# Sheet1.net
KiCad netlist of a schematic drawn in Altium Designer
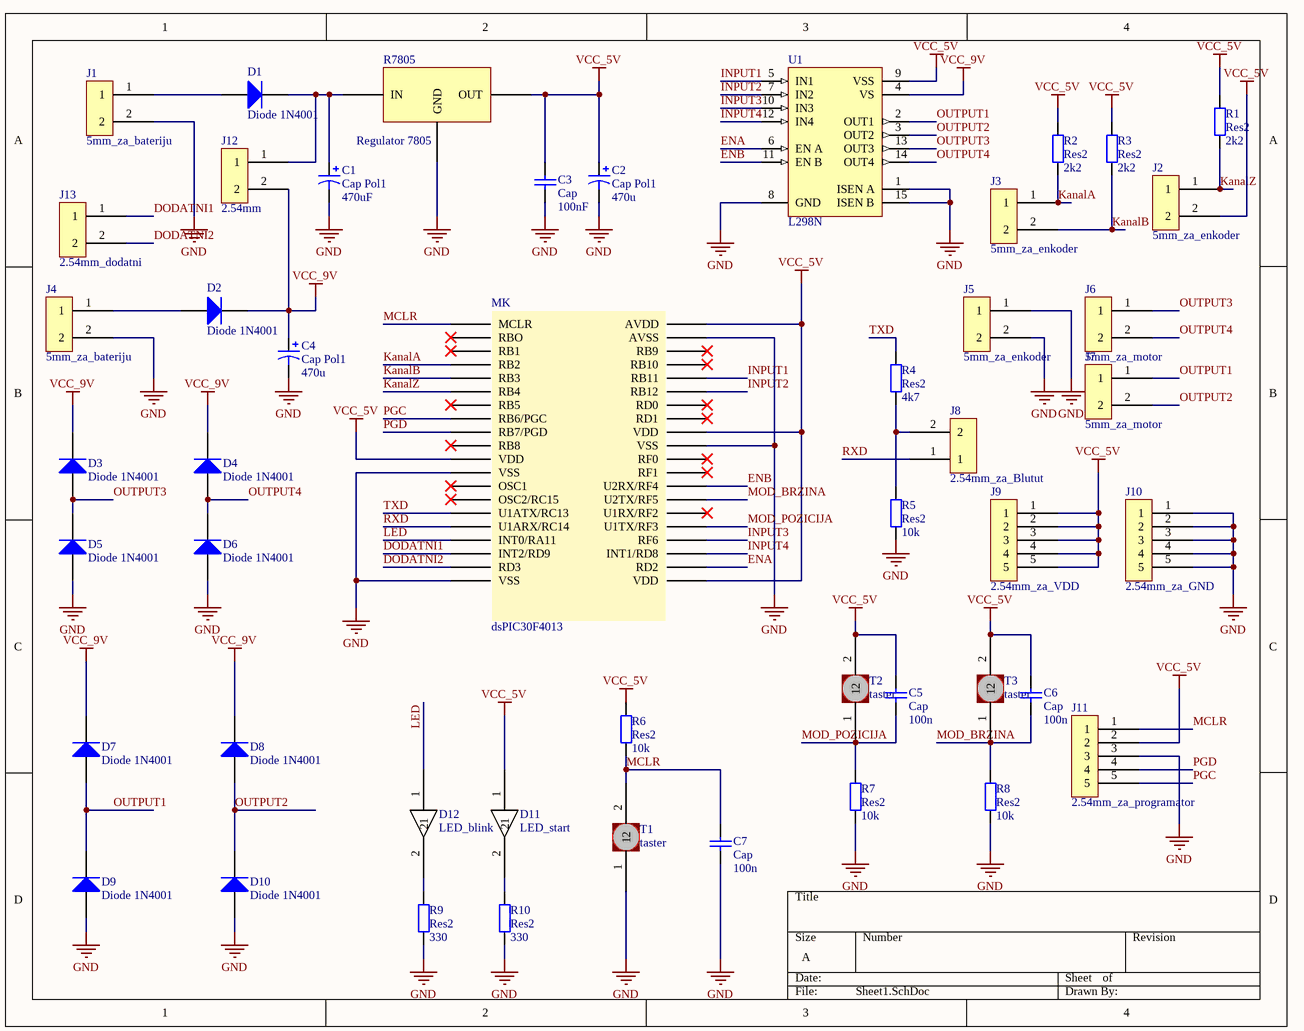
[diagram p0: Sheet1.SchDoc]

(export (version "E")
  (design (tool "Eeschema 10.0.6"))
  (components
    (comp (ref "C1")
      (value "Cap Pol1")
      (footprint "RB7.6-15")
      (description "Polarized Capacitor (Radial)")
      (fields (field (name "ALTIUM_VALUE") "470uF") (field (name "PUBLISHER") "Altium Limited"))
      (libsource (lib "Miscellaneous Devices") (part "Cap Pol1"))
    )
    (comp (ref "C2")
      (value "Cap Pol1")
      (footprint "RB7.6-15")
      (description "Polarized Capacitor (Radial)")
      (fields (field (name "ALTIUM_VALUE") "470u") (field (name "PUBLISHER") "Altium Limited"))
      (libsource (lib "Miscellaneous Devices") (part "Cap Pol1"))
    )
    (comp (ref "C3")
      (value "Cap")
      (footprint "RAD-0.3")
      (description "Capacitor")
      (fields (field (name "ALTIUM_VALUE") "100nF") (field (name "PUBLISHER") "Altium Limited"))
      (libsource (lib "Miscellaneous Devices") (part "Cap"))
    )
    (comp (ref "C4")
      (value "Cap Pol1")
      (footprint "RB7.6-15")
      (description "Polarized Capacitor (Radial)")
      (fields (field (name "ALTIUM_VALUE") "470u") (field (name "PUBLISHER") "Altium Limited"))
      (libsource (lib "Miscellaneous Devices") (part "Cap Pol1"))
    )
    (comp (ref "C5")
      (value "Cap")
      (footprint "RAD-0.3")
      (description "Capacitor")
      (fields (field (name "ALTIUM_VALUE") "100n") (field (name "PUBLISHER") "Altium Limited"))
      (libsource (lib "Miscellaneous Devices") (part "Cap"))
    )
    (comp (ref "C6")
      (value "Cap")
      (footprint "RAD-0.3")
      (description "Capacitor")
      (fields (field (name "ALTIUM_VALUE") "100n") (field (name "PUBLISHER") "Altium Limited"))
      (libsource (lib "Miscellaneous Devices") (part "Cap"))
    )
    (comp (ref "C7")
      (value "Cap")
      (footprint "RAD-0.3")
      (description "Capacitor")
      (fields (field (name "ALTIUM_VALUE") "100n") (field (name "PUBLISHER") "Altium Limited"))
      (libsource (lib "Miscellaneous Devices") (part "Cap"))
    )
    (comp (ref "D1")
      (value "Diode 1N4001")
      (footprint "DO-41")
      (description "1 Amp General Purpose Rectifier")
      (fields (field (name "PUBLISHER") "Altium Limited"))
      (libsource (lib "Miscellaneous Devices") (part "Diode 1N4001"))
    )
    (comp (ref "D2")
      (value "Diode 1N4001")
      (footprint "DO-41")
      (description "1 Amp General Purpose Rectifier")
      (fields (field (name "PUBLISHER") "Altium Limited"))
      (libsource (lib "Miscellaneous Devices") (part "Diode 1N4001"))
    )
    (comp (ref "D3")
      (value "Diode 1N4001")
      (footprint "DO-41")
      (description "1 Amp General Purpose Rectifier")
      (fields (field (name "PUBLISHER") "Altium Limited"))
      (libsource (lib "Miscellaneous Devices") (part "Diode 1N4001"))
    )
    (comp (ref "D4")
      (value "Diode 1N4001")
      (footprint "DO-41")
      (description "1 Amp General Purpose Rectifier")
      (fields (field (name "PUBLISHER") "Altium Limited"))
      (libsource (lib "Miscellaneous Devices") (part "Diode 1N4001"))
    )
    (comp (ref "D5")
      (value "Diode 1N4001")
      (footprint "DO-41")
      (description "1 Amp General Purpose Rectifier")
      (fields (field (name "PUBLISHER") "Altium Limited"))
      (libsource (lib "Miscellaneous Devices") (part "Diode 1N4001"))
    )
    (comp (ref "D6")
      (value "Diode 1N4001")
      (footprint "DO-41")
      (description "1 Amp General Purpose Rectifier")
      (fields (field (name "PUBLISHER") "Altium Limited"))
      (libsource (lib "Miscellaneous Devices") (part "Diode 1N4001"))
    )
    (comp (ref "D7")
      (value "Diode 1N4001")
      (footprint "DO-41")
      (description "1 Amp General Purpose Rectifier")
      (fields (field (name "PUBLISHER") "Altium Limited"))
      (libsource (lib "Miscellaneous Devices") (part "Diode 1N4001"))
    )
    (comp (ref "D8")
      (value "Diode 1N4001")
      (footprint "DO-41")
      (description "1 Amp General Purpose Rectifier")
      (fields (field (name "PUBLISHER") "Altium Limited"))
      (libsource (lib "Miscellaneous Devices") (part "Diode 1N4001"))
    )
    (comp (ref "D9")
      (value "Diode 1N4001")
      (footprint "DO-41")
      (description "1 Amp General Purpose Rectifier")
      (fields (field (name "PUBLISHER") "Altium Limited"))
      (libsource (lib "Miscellaneous Devices") (part "Diode 1N4001"))
    )
    (comp (ref "D10")
      (value "Diode 1N4001")
      (footprint "DO-41")
      (description "1 Amp General Purpose Rectifier")
      (fields (field (name "PUBLISHER") "Altium Limited"))
      (libsource (lib "Miscellaneous Devices") (part "Diode 1N4001"))
    )
    (comp (ref "D11")
      (value "LED_start")
      (footprint "PcbLib5:PCBComponent_1")
      (libsource (lib "Schlib5") (part "Component_1"))
    )
    (comp (ref "D12")
      (value "LED_blink")
      (footprint "PcbLib5:PCBComponent_1")
      (libsource (lib "Schlib5") (part "Component_1"))
    )
    (comp (ref "J1")
      (value "5mm_za_bateriju")
      (footprint "PcbLib4:PCBComponent_1")
      (libsource (lib "Schlib4") (part "Component_1"))
    )
    (comp (ref "J2")
      (value "5mm_za_enkoder")
      (footprint "PcbLib4:PCBComponent_1")
      (libsource (lib "Schlib4") (part "Component_1"))
    )
    (comp (ref "J3")
      (value "5mm_za_enkoder")
      (footprint "PcbLib4:PCBComponent_1")
      (libsource (lib "Schlib4") (part "Component_1"))
    )
    (comp (ref "J4")
      (value "5mm_za_bateriju")
      (footprint "PcbLib4:PCBComponent_1")
      (libsource (lib "Schlib4") (part "Component_1"))
    )
    (comp (ref "J5")
      (value "5mm_za_enkoder")
      (footprint "PcbLib4:PCBComponent_1")
      (libsource (lib "Schlib4") (part "Component_1"))
    )
    (comp (ref "J6")
      (value "5mm_za_motor")
      (footprint "PcbLib4:PCBComponent_1")
      (libsource (lib "Schlib4") (part "Component_1"))
    )
    (comp (ref "J7")
      (value "5mm_za_motor")
      (footprint "PcbLib4:PCBComponent_1")
      (libsource (lib "Schlib4") (part "Component_1"))
    )
    (comp (ref "J8")
      (value "2.54mm_za_Blutut")
      (footprint "PcbLib3:PCBComponent_1")
      (libsource (lib "") (part "Component_1_1"))
    )
    (comp (ref "J9")
      (value "2.54mm_za_VDD")
      (footprint "PcbLib7:PCBComponent_1")
      (libsource (lib "Schlib7") (part "Component_1"))
    )
    (comp (ref "J10")
      (value "2.54mm_za_GND")
      (footprint "PcbLib7:PCBComponent_1")
      (libsource (lib "Schlib7") (part "Component_1"))
    )
    (comp (ref "J11")
      (value "2.54mm_za_programator")
      (footprint "PcbLib7:PCBComponent_1")
      (libsource (lib "Schlib7") (part "Component_1"))
    )
    (comp (ref "J12")
      (value "2.54mm")
      (footprint "PcbLib3:PCBComponent_1")
      (libsource (lib "Schlib1") (part "Component_1"))
    )
    (comp (ref "J13")
      (value "2.54mm_dodatni")
      (footprint "PcbLib3:PCBComponent_1")
      (libsource (lib "Schlib1") (part "Component_1"))
    )
    (comp (ref "MK")
      (value "dsPIC30F4013")
      (footprint "PcbLib1:PCBComponent_1")
      (libsource (lib "Schlib3") (part "Component_1"))
    )
    (comp (ref "R1")
      (value "Res2")
      (footprint "AXIAL-0.4")
      (description "Resistor")
      (fields (field (name "ALTIUM_VALUE") "2k2") (field (name "PUBLISHER") "Altium Limited"))
      (libsource (lib "Miscellaneous Devices") (part "Res2"))
    )
    (comp (ref "R2")
      (value "Res2")
      (footprint "AXIAL-0.4")
      (description "Resistor")
      (fields (field (name "ALTIUM_VALUE") "2k2") (field (name "PUBLISHER") "Altium Limited"))
      (libsource (lib "Miscellaneous Devices") (part "Res2"))
    )
    (comp (ref "R3")
      (value "Res2")
      (footprint "AXIAL-0.4")
      (description "Resistor")
      (fields (field (name "ALTIUM_VALUE") "2k2") (field (name "PUBLISHER") "Altium Limited"))
      (libsource (lib "Miscellaneous Devices") (part "Res2"))
    )
    (comp (ref "R4")
      (value "Res2")
      (footprint "AXIAL-0.4")
      (description "Resistor")
      (fields (field (name "ALTIUM_VALUE") "4k7") (field (name "PUBLISHER") "Altium Limited"))
      (libsource (lib "Miscellaneous Devices") (part "Res2"))
    )
    (comp (ref "R5")
      (value "Res2")
      (footprint "AXIAL-0.4")
      (description "Resistor")
      (fields (field (name "ALTIUM_VALUE") "10k") (field (name "PUBLISHER") "Altium Limited"))
      (libsource (lib "Miscellaneous Devices") (part "Res2"))
    )
    (comp (ref "R6")
      (value "Res2")
      (footprint "AXIAL-0.4")
      (description "Resistor")
      (fields (field (name "ALTIUM_VALUE") "10k") (field (name "PUBLISHER") "Altium Limited"))
      (libsource (lib "Miscellaneous Devices") (part "Res2"))
    )
    (comp (ref "R7")
      (value "Res2")
      (footprint "AXIAL-0.4")
      (description "Resistor")
      (fields (field (name "ALTIUM_VALUE") "10k") (field (name "PUBLISHER") "Altium Limited"))
      (libsource (lib "Miscellaneous Devices") (part "Res2"))
    )
    (comp (ref "R8")
      (value "Res2")
      (footprint "AXIAL-0.4")
      (description "Resistor")
      (fields (field (name "ALTIUM_VALUE") "10k") (field (name "PUBLISHER") "Altium Limited"))
      (libsource (lib "Miscellaneous Devices") (part "Res2"))
    )
    (comp (ref "R9")
      (value "Res2")
      (footprint "AXIAL-0.4")
      (description "Resistor")
      (fields (field (name "ALTIUM_VALUE") "330") (field (name "PUBLISHER") "Altium Limited"))
      (libsource (lib "Miscellaneous Devices") (part "Res2"))
    )
    (comp (ref "R10")
      (value "Res2")
      (footprint "AXIAL-0.4")
      (description "Resistor")
      (fields (field (name "ALTIUM_VALUE") "330") (field (name "PUBLISHER") "Altium Limited"))
      (libsource (lib "Miscellaneous Devices") (part "Res2"))
    )
    (comp (ref "R7805")
      (value "Regulator 7805")
      (footprint "PCBComponent_1")
      (libsource (lib "Schlib2") (part "Component_1"))
    )
    (comp (ref "T1")
      (value "taster")
      (footprint "PcbLib6:PCBComponent_1")
      (libsource (lib "Schlib6") (part "Component_1"))
    )
    (comp (ref "T2")
      (value "taster")
      (footprint "PcbLib6:PCBComponent_1")
      (libsource (lib "Schlib6") (part "Component_1"))
    )
    (comp (ref "T3")
      (value "taster")
      (footprint "PcbLib6:PCBComponent_1")
      (libsource (lib "Schlib6") (part "Component_1"))
    )
    (comp (ref "U1")
      (value "L298N")
      (footprint "Multiwatt15V")
      (description "Dual Full Bridge Driver")
      (fields (field (name "PUBLISHER") "Altium Limited"))
      (libsource (lib "ST Interface DC Motor Controller") (part "L298N"))
    )
  )
  (nets
    (net (code "1") (name "/DODATNI1") (class "Default")
      (node (ref "J13") (pin "1") (pinfunction "1_1") (pintype "passive"))
      (node (ref "MK") (pin "18") (pinfunction "INT2/RD9_18") (pintype "passive"))
    )
    (net (code "2") (name "/DODATNI2") (class "Default")
      (node (ref "J13") (pin "2") (pinfunction "2_2") (pintype "passive"))
      (node (ref "MK") (pin "19") (pinfunction "RD3_19") (pintype "passive"))
    )
    (net (code "3") (name "/ENA") (class "Default")
      (node (ref "MK") (pin "22") (pinfunction "RD2_22") (pintype "passive"))
      (node (ref "U1") (pin "6") (pinfunction "EN_A_6") (pintype "input"))
    )
    (net (code "4") (name "/ENB") (class "Default")
      (node (ref "MK") (pin "28") (pinfunction "U2RX/RF4_28") (pintype "passive"))
      (node (ref "U1") (pin "11") (pinfunction "EN_B_11") (pintype "input"))
    )
    (net (code "5") (name "/INPUT1") (class "Default")
      (node (ref "MK") (pin "36") (pinfunction "RB11_36") (pintype "passive"))
      (node (ref "U1") (pin "5") (pinfunction "IN1_5") (pintype "input"))
    )
    (net (code "6") (name "/INPUT2") (class "Default")
      (node (ref "MK") (pin "35") (pinfunction "RB12_35") (pintype "passive"))
      (node (ref "U1") (pin "7") (pinfunction "IN2_7") (pintype "input"))
    )
    (net (code "7") (name "/INPUT3") (class "Default")
      (node (ref "MK") (pin "24") (pinfunction "RF6_24") (pintype "passive"))
      (node (ref "U1") (pin "10") (pinfunction "IN3_10") (pintype "input"))
    )
    (net (code "8") (name "/INPUT4") (class "Default")
      (node (ref "MK") (pin "23") (pinfunction "INT1/RD8_23") (pintype "passive"))
      (node (ref "U1") (pin "12") (pinfunction "IN4_12") (pintype "input"))
    )
    (net (code "9") (name "/KanalA") (class "Default")
      (node (ref "J3") (pin "1") (pinfunction "1_1") (pintype "passive"))
      (node (ref "MK") (pin "4") (pinfunction "RB2_4") (pintype "passive"))
      (node (ref "R2") (pin "1") (pinfunction "1_1") (pintype "passive"))
    )
    (net (code "10") (name "/KanalB") (class "Default")
      (node (ref "J3") (pin "2") (pinfunction "2_2") (pintype "passive"))
      (node (ref "MK") (pin "5") (pinfunction "RB3_5") (pintype "passive"))
      (node (ref "R3") (pin "1") (pinfunction "1_1") (pintype "passive"))
    )
    (net (code "11") (name "/KanalZ") (class "Default")
      (node (ref "J2") (pin "1") (pinfunction "1_1") (pintype "passive"))
      (node (ref "MK") (pin "6") (pinfunction "RB4_6") (pintype "passive"))
      (node (ref "R1") (pin "1") (pinfunction "1_1") (pintype "passive"))
    )
    (net (code "12") (name "/LED") (class "Default")
      (node (ref "D12") (pin "1") (pinfunction "1_1") (pintype "passive"))
      (node (ref "MK") (pin "17") (pinfunction "INT0/RA11_17") (pintype "passive"))
    )
    (net (code "13") (name "/MCLR") (class "Default")
      (node (ref "C7") (pin "2") (pinfunction "2_2") (pintype "passive"))
      (node (ref "J11") (pin "1") (pinfunction "1_1") (pintype "passive"))
      (node (ref "MK") (pin "1") (pinfunction "MCLR_1") (pintype "passive"))
      (node (ref "R6") (pin "1") (pinfunction "1_1") (pintype "passive"))
      (node (ref "T1") (pin "2") (pinfunction "2_2") (pintype "passive"))
    )
    (net (code "14") (name "/MOD_BRZINA") (class "Default")
      (node (ref "C6") (pin "1") (pinfunction "1_1") (pintype "passive"))
      (node (ref "MK") (pin "27") (pinfunction "U2TX/RF5_27") (pintype "passive"))
      (node (ref "R8") (pin "2") (pinfunction "2_2") (pintype "passive"))
      (node (ref "T3") (pin "1") (pinfunction "1_1") (pintype "passive"))
    )
    (net (code "15") (name "/MOD_POZICIJA") (class "Default")
      (node (ref "C5") (pin "1") (pinfunction "1_1") (pintype "passive"))
      (node (ref "MK") (pin "25") (pinfunction "U1TX/RF3_25") (pintype "passive"))
      (node (ref "R7") (pin "2") (pinfunction "2_2") (pintype "passive"))
      (node (ref "T2") (pin "1") (pinfunction "1_1") (pintype "passive"))
    )
    (net (code "16") (name "/OUTPUT1") (class "Default")
      (node (ref "D7") (pin "1") (pinfunction "A_1") (pintype "passive"))
      (node (ref "D9") (pin "2") (pinfunction "K_2") (pintype "passive"))
      (node (ref "J7") (pin "1") (pinfunction "1_1") (pintype "passive"))
      (node (ref "U1") (pin "2") (pinfunction "OUT1_2") (pintype "output"))
    )
    (net (code "17") (name "/OUTPUT2") (class "Default")
      (node (ref "D10") (pin "2") (pinfunction "K_2") (pintype "passive"))
      (node (ref "D8") (pin "1") (pinfunction "A_1") (pintype "passive"))
      (node (ref "J7") (pin "2") (pinfunction "2_2") (pintype "passive"))
      (node (ref "U1") (pin "3") (pinfunction "OUT2_3") (pintype "output"))
    )
    (net (code "18") (name "/OUTPUT3") (class "Default")
      (node (ref "D3") (pin "1") (pinfunction "A_1") (pintype "passive"))
      (node (ref "D5") (pin "2") (pinfunction "K_2") (pintype "passive"))
      (node (ref "J6") (pin "1") (pinfunction "1_1") (pintype "passive"))
      (node (ref "U1") (pin "13") (pinfunction "OUT3_13") (pintype "output"))
    )
    (net (code "19") (name "/OUTPUT4") (class "Default")
      (node (ref "D4") (pin "1") (pinfunction "A_1") (pintype "passive"))
      (node (ref "D6") (pin "2") (pinfunction "K_2") (pintype "passive"))
      (node (ref "J6") (pin "2") (pinfunction "2_2") (pintype "passive"))
      (node (ref "U1") (pin "14") (pinfunction "OUT4_14") (pintype "output"))
    )
    (net (code "20") (name "/PGC") (class "Default")
      (node (ref "J11") (pin "5") (pinfunction "5_5") (pintype "passive"))
      (node (ref "MK") (pin "8") (pinfunction "RB6/PGC_8") (pintype "passive"))
    )
    (net (code "21") (name "/PGD") (class "Default")
      (node (ref "J11") (pin "4") (pinfunction "4_4") (pintype "passive"))
      (node (ref "MK") (pin "9") (pinfunction "RB7/PGD_9") (pintype "passive"))
    )
    (net (code "22") (name "/RXD") (class "Default")
      (node (ref "J8") (pin "1") (pinfunction "1_1") (pintype "passive"))
      (node (ref "MK") (pin "16") (pinfunction "U1ARX/RC14_16") (pintype "passive"))
    )
    (net (code "23") (name "/TXD") (class "Default")
      (node (ref "MK") (pin "15") (pinfunction "U1ATX/RC13_15") (pintype "passive"))
      (node (ref "R4") (pin "2") (pinfunction "2_2") (pintype "passive"))
    )
    (net (code "24") (name "GND") (class "Default")
      (node (ref "C1") (pin "2") (pinfunction "2_2") (pintype "passive"))
      (node (ref "C2") (pin "2") (pinfunction "2_2") (pintype "passive"))
      (node (ref "C3") (pin "1") (pinfunction "1_1") (pintype "passive"))
      (node (ref "C4") (pin "2") (pinfunction "2_2") (pintype "passive"))
      (node (ref "C7") (pin "1") (pinfunction "1_1") (pintype "passive"))
      (node (ref "D10") (pin "1") (pinfunction "A_1") (pintype "passive"))
      (node (ref "D5") (pin "1") (pinfunction "A_1") (pintype "passive"))
      (node (ref "D6") (pin "1") (pinfunction "A_1") (pintype "passive"))
      (node (ref "D9") (pin "1") (pinfunction "A_1") (pintype "passive"))
      (node (ref "J1") (pin "2") (pinfunction "2_2") (pintype "passive"))
      (node (ref "J10") (pin "1") (pinfunction "1_1") (pintype "passive"))
      (node (ref "J10") (pin "2") (pinfunction "2_2") (pintype "passive"))
      (node (ref "J10") (pin "3") (pinfunction "3_3") (pintype "passive"))
      (node (ref "J10") (pin "4") (pinfunction "4_4") (pintype "passive"))
      (node (ref "J10") (pin "5") (pinfunction "5_5") (pintype "passive"))
      (node (ref "J11") (pin "3") (pinfunction "3_3") (pintype "passive"))
      (node (ref "J4") (pin "2") (pinfunction "2_2") (pintype "passive"))
      (node (ref "J5") (pin "1") (pinfunction "1_1") (pintype "passive"))
      (node (ref "J5") (pin "2") (pinfunction "2_2") (pintype "passive"))
      (node (ref "MK") (pin "12") (pinfunction "VSS_12") (pintype "passive"))
      (node (ref "MK") (pin "20") (pinfunction "VSS_20") (pintype "passive"))
      (node (ref "MK") (pin "31") (pinfunction "VSS_31") (pintype "passive"))
      (node (ref "MK") (pin "39") (pinfunction "AVSS_39") (pintype "passive"))
      (node (ref "R10") (pin "1") (pinfunction "1_1") (pintype "passive"))
      (node (ref "R5") (pin "1") (pinfunction "1_1") (pintype "passive"))
      (node (ref "R7") (pin "1") (pinfunction "1_1") (pintype "passive"))
      (node (ref "R7805") (pin "2") (pinfunction "GND_2") (pintype "passive"))
      (node (ref "R8") (pin "1") (pinfunction "1_1") (pintype "passive"))
      (node (ref "R9") (pin "1") (pinfunction "1_1") (pintype "passive"))
      (node (ref "T1") (pin "1") (pinfunction "1_1") (pintype "passive"))
      (node (ref "U1") (pin "1") (pinfunction "ISEN_A_1") (pintype "passive"))
      (node (ref "U1") (pin "15") (pinfunction "ISEN_B_15") (pintype "passive"))
      (node (ref "U1") (pin "8") (pinfunction "GND_8") (pintype "power_in"))
    )
    (net (code "25") (name "Net-(D1-A)") (class "Default")
      (node (ref "D1") (pin "1") (pinfunction "A_1") (pintype "passive"))
      (node (ref "J1") (pin "1") (pinfunction "1_1") (pintype "passive"))
    )
    (net (code "26") (name "Net-(D1-K)") (class "Default")
      (node (ref "C1") (pin "1") (pinfunction "1_1") (pintype "passive"))
      (node (ref "D1") (pin "2") (pinfunction "K_2") (pintype "passive"))
      (node (ref "J12") (pin "1") (pinfunction "1_1") (pintype "passive"))
      (node (ref "R7805") (pin "1") (pinfunction "IN_1") (pintype "passive"))
    )
    (net (code "27") (name "Net-(D2-A)") (class "Default")
      (node (ref "D2") (pin "1") (pinfunction "A_1") (pintype "passive"))
      (node (ref "J4") (pin "1") (pinfunction "1_1") (pintype "passive"))
    )
    (net (code "28") (name "Net-(D11-Pad2)") (class "Default")
      (node (ref "D11") (pin "2") (pinfunction "2_2") (pintype "passive"))
      (node (ref "R10") (pin "2") (pinfunction "2_2") (pintype "passive"))
    )
    (net (code "29") (name "Net-(D12-Pad2)") (class "Default")
      (node (ref "D12") (pin "2") (pinfunction "2_2") (pintype "passive"))
      (node (ref "R9") (pin "2") (pinfunction "2_2") (pintype "passive"))
    )
    (net (code "30") (name "Net-(J8-Pad2)") (class "Default")
      (node (ref "J8") (pin "2") (pinfunction "2_2") (pintype "passive"))
      (node (ref "R4") (pin "1") (pinfunction "1_1") (pintype "passive"))
      (node (ref "R5") (pin "2") (pinfunction "2_2") (pintype "passive"))
    )
    (net (code "31") (name "VCC_5V") (class "Default")
      (node (ref "C2") (pin "1") (pinfunction "1_1") (pintype "passive"))
      (node (ref "C3") (pin "2") (pinfunction "2_2") (pintype "passive"))
      (node (ref "C5") (pin "2") (pinfunction "2_2") (pintype "passive"))
      (node (ref "C6") (pin "2") (pinfunction "2_2") (pintype "passive"))
      (node (ref "D11") (pin "1") (pinfunction "1_1") (pintype "passive"))
      (node (ref "J11") (pin "2") (pinfunction "2_2") (pintype "passive"))
      (node (ref "J2") (pin "2") (pinfunction "2_2") (pintype "passive"))
      (node (ref "J9") (pin "1") (pinfunction "1_1") (pintype "passive"))
      (node (ref "J9") (pin "2") (pinfunction "2_2") (pintype "passive"))
      (node (ref "J9") (pin "3") (pinfunction "3_3") (pintype "passive"))
      (node (ref "J9") (pin "4") (pinfunction "4_4") (pintype "passive"))
      (node (ref "J9") (pin "5") (pinfunction "5_5") (pintype "passive"))
      (node (ref "MK") (pin "11") (pinfunction "VDD_11") (pintype "passive"))
      (node (ref "MK") (pin "21") (pinfunction "VDD_21") (pintype "passive"))
      (node (ref "MK") (pin "32") (pinfunction "VDD_32") (pintype "passive"))
      (node (ref "MK") (pin "40") (pinfunction "AVDD_40") (pintype "passive"))
      (node (ref "R1") (pin "2") (pinfunction "2_2") (pintype "passive"))
      (node (ref "R2") (pin "2") (pinfunction "2_2") (pintype "passive"))
      (node (ref "R3") (pin "2") (pinfunction "2_2") (pintype "passive"))
      (node (ref "R6") (pin "2") (pinfunction "2_2") (pintype "passive"))
      (node (ref "R7805") (pin "3") (pinfunction "OUT_3") (pintype "passive"))
      (node (ref "T2") (pin "2") (pinfunction "2_2") (pintype "passive"))
      (node (ref "T3") (pin "2") (pinfunction "2_2") (pintype "passive"))
      (node (ref "U1") (pin "9") (pinfunction "VSS_9") (pintype "power_in"))
    )
    (net (code "32") (name "VCC_9V") (class "Default")
      (node (ref "C4") (pin "1") (pinfunction "1_1") (pintype "passive"))
      (node (ref "D2") (pin "2") (pinfunction "K_2") (pintype "passive"))
      (node (ref "D3") (pin "2") (pinfunction "K_2") (pintype "passive"))
      (node (ref "D4") (pin "2") (pinfunction "K_2") (pintype "passive"))
      (node (ref "D7") (pin "2") (pinfunction "K_2") (pintype "passive"))
      (node (ref "D8") (pin "2") (pinfunction "K_2") (pintype "passive"))
      (node (ref "J12") (pin "2") (pinfunction "2_2") (pintype "passive"))
      (node (ref "U1") (pin "4") (pinfunction "VS_4") (pintype "power_in"))
    )
    (net (code "33") (name "unconnected-(MK-OSC1-Pad13)") (class "Default")
      (node (ref "MK") (pin "13") (pinfunction "OSC1_13") (pintype "passive+no_connect"))
    )
    (net (code "34") (name "unconnected-(MK-OSC2{slash}RC15-Pad14)") (class "Default")
      (node (ref "MK") (pin "14") (pinfunction "OSC2/RC15_14") (pintype "passive+no_connect"))
    )
    (net (code "35") (name "unconnected-(MK-RB1-Pad3)") (class "Default")
      (node (ref "MK") (pin "3") (pinfunction "RB1_3") (pintype "passive+no_connect"))
    )
    (net (code "36") (name "unconnected-(MK-RB5-Pad7)") (class "Default")
      (node (ref "MK") (pin "7") (pinfunction "RB5_7") (pintype "passive+no_connect"))
    )
    (net (code "37") (name "unconnected-(MK-RB8-Pad10)") (class "Default")
      (node (ref "MK") (pin "10") (pinfunction "RB8_10") (pintype "passive+no_connect"))
    )
    (net (code "38") (name "unconnected-(MK-RB9-Pad38)") (class "Default")
      (node (ref "MK") (pin "38") (pinfunction "RB9_38") (pintype "passive+no_connect"))
    )
    (net (code "39") (name "unconnected-(MK-RB10-Pad37)") (class "Default")
      (node (ref "MK") (pin "37") (pinfunction "RB10_37") (pintype "passive+no_connect"))
    )
    (net (code "40") (name "unconnected-(MK-RBO-Pad2)") (class "Default")
      (node (ref "MK") (pin "2") (pinfunction "RBO_2") (pintype "passive+no_connect"))
    )
    (net (code "41") (name "unconnected-(MK-RD0-Pad34)") (class "Default")
      (node (ref "MK") (pin "34") (pinfunction "RD0_34") (pintype "passive+no_connect"))
    )
    (net (code "42") (name "unconnected-(MK-RD1-Pad33)") (class "Default")
      (node (ref "MK") (pin "33") (pinfunction "RD1_33") (pintype "passive+no_connect"))
    )
    (net (code "43") (name "unconnected-(MK-RF0-Pad30)") (class "Default")
      (node (ref "MK") (pin "30") (pinfunction "RF0_30") (pintype "passive+no_connect"))
    )
    (net (code "44") (name "unconnected-(MK-RF1-Pad29)") (class "Default")
      (node (ref "MK") (pin "29") (pinfunction "RF1_29") (pintype "passive+no_connect"))
    )
    (net (code "45") (name "unconnected-(MK-U1RX{slash}RF2-Pad26)") (class "Default")
      (node (ref "MK") (pin "26") (pinfunction "U1RX/RF2_26") (pintype "passive+no_connect"))
    )
  )
)
